# Juricic_Ulaz.net
KiCad netlist of a schematic drawn in Altium Designer
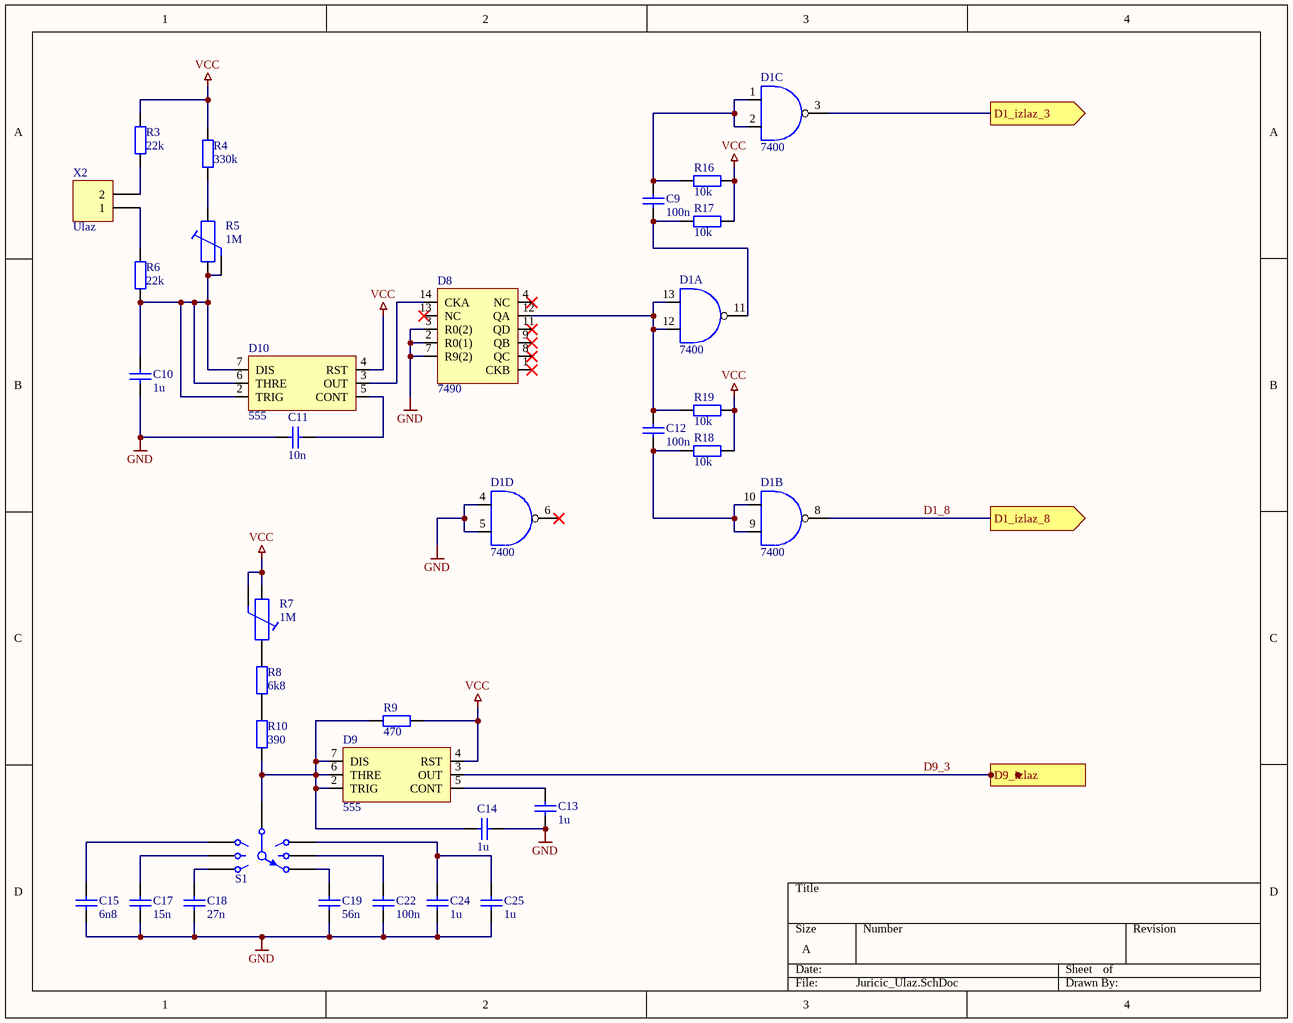
[diagram p0: Juricic_Ulaz.SchDoc]

(export (version "E")
  (design (tool "Eeschema 10.0.6"))
  (components
    (comp (ref "C9")
      (value "100n")
      (footprint "C0805")
      (description "100n capacitor")
      (fields (field (name "PUBLISHER") "Altium Limited"))
      (libsource (lib "Miscellaneous Devices") (part "Cap"))
    )
    (comp (ref "C10")
      (value "1u")
      (footprint "C0805")
      (description "1u capacitor")
      (fields (field (name "PUBLISHER") "Altium Limited"))
      (libsource (lib "Miscellaneous Devices") (part "Cap"))
    )
    (comp (ref "C11")
      (value "10n")
      (footprint "C0805")
      (description "10n capacitor")
      (fields (field (name "PUBLISHER") "Altium Limited"))
      (libsource (lib "Miscellaneous Devices") (part "Cap"))
    )
    (comp (ref "C12")
      (value "100n")
      (footprint "C0805")
      (description "100n capacitor")
      (fields (field (name "PUBLISHER") "Altium Limited"))
      (libsource (lib "Miscellaneous Devices") (part "Cap"))
    )
    (comp (ref "C13")
      (value "1u")
      (footprint "C0805")
      (description "1u capacitor")
      (fields (field (name "PUBLISHER") "Altium Limited"))
      (libsource (lib "Miscellaneous Devices") (part "Cap"))
    )
    (comp (ref "C14")
      (value "1u")
      (footprint "C0805")
      (description "1u capacitor")
      (fields (field (name "PUBLISHER") "Altium Limited"))
      (libsource (lib "Miscellaneous Devices") (part "Cap"))
    )
    (comp (ref "C15")
      (value "6n8")
      (footprint "C0805")
      (description "6n8 capacitor")
      (fields (field (name "PUBLISHER") "Altium Limited"))
      (libsource (lib "Miscellaneous Devices") (part "Cap"))
    )
    (comp (ref "C17")
      (value "15n")
      (footprint "C0805")
      (description "15n capacitor")
      (fields (field (name "PUBLISHER") "Altium Limited"))
      (libsource (lib "Miscellaneous Devices") (part "Cap"))
    )
    (comp (ref "C18")
      (value "27n")
      (footprint "C0805")
      (description "27n capacitor")
      (fields (field (name "PUBLISHER") "Altium Limited"))
      (libsource (lib "Miscellaneous Devices") (part "Cap"))
    )
    (comp (ref "C19")
      (value "56n")
      (footprint "C0805")
      (description "56n capacitor")
      (fields (field (name "PUBLISHER") "Altium Limited"))
      (libsource (lib "Miscellaneous Devices") (part "Cap"))
    )
    (comp (ref "C22")
      (value "100n")
      (footprint "C0805")
      (description "100n capacitor")
      (fields (field (name "PUBLISHER") "Altium Limited"))
      (libsource (lib "Miscellaneous Devices") (part "Cap"))
    )
    (comp (ref "C24")
      (value "1u")
      (footprint "C0805")
      (description "1u capacitor")
      (fields (field (name "PUBLISHER") "Altium Limited"))
      (libsource (lib "Miscellaneous Devices") (part "Cap"))
    )
    (comp (ref "C25")
      (value "1u")
      (footprint "C0805")
      (description "1u capacitor")
      (fields (field (name "PUBLISHER") "Altium Limited"))
      (libsource (lib "Miscellaneous Devices") (part "Cap"))
    )
    (comp (ref "D1")
      (value "7400")
      (footprint "DIP-14")
      (description "NI sklop")
      (libsource (lib "Indikator_lib") (part "7400"))
    )
    (comp (ref "D8")
      (value "7490")
      (footprint "DIP-14")
      (description "Dekadsko/binarno brojilo")
      (libsource (lib "Indikator_lib") (part "7490"))
    )
    (comp (ref "D9") (value "555") (footprint "DIP-8") (libsource (lib "Indikator_lib") (part "555")))
    (comp (ref "D10") (value "555") (footprint "DIP-8") (libsource (lib "Indikator_lib") (part "555")))
    (comp (ref "R3")
      (value "22k")
      (footprint "AXIAL-0.4")
      (description "22k resistor")
      (fields (field (name "PUBLISHER") "Altium Limited"))
      (libsource (lib "") (part "Res2_2"))
    )
    (comp (ref "R4")
      (value "330k")
      (footprint "AXIAL-0.4")
      (description "330k resistor")
      (fields (field (name "PUBLISHER") "Altium Limited"))
      (libsource (lib "") (part "Res2_2"))
    )
    (comp (ref "R5") (value "1M") (footprint "Trimmer") (libsource (lib "Juricic_Ivan") (part "Trimmer")))
    (comp (ref "R6")
      (value "22k")
      (footprint "AXIAL-0.4")
      (description "22k resistor")
      (fields (field (name "PUBLISHER") "Altium Limited"))
      (libsource (lib "Miscellaneous Devices") (part "Res2"))
    )
    (comp (ref "R7") (value "1M") (footprint "Trimmer") (libsource (lib "Juricic_Ivan") (part "Trimmer")))
    (comp (ref "R8")
      (value "6k8")
      (footprint "AXIAL-0.4")
      (description "6k8 resistor")
      (fields (field (name "PUBLISHER") "Altium Limited"))
      (libsource (lib "Miscellaneous Devices") (part "Res2"))
    )
    (comp (ref "R9")
      (value "470")
      (footprint "AXIAL-0.4")
      (description "470 resistor")
      (fields (field (name "PUBLISHER") "Altium Limited"))
      (libsource (lib "") (part "Res2_1"))
    )
    (comp (ref "R10")
      (value "390")
      (footprint "AXIAL-0.4")
      (description "390 resistor")
      (fields (field (name "PUBLISHER") "Altium Limited"))
      (libsource (lib "Miscellaneous Devices") (part "Res2"))
    )
    (comp (ref "R16")
      (value "10k")
      (footprint "AXIAL-0.4")
      (description "10k resistor")
      (fields (field (name "PUBLISHER") "Altium Limited"))
      (libsource (lib "") (part "Res2_1"))
    )
    (comp (ref "R17")
      (value "10k")
      (footprint "AXIAL-0.4")
      (description "10k resistor")
      (fields (field (name "PUBLISHER") "Altium Limited"))
      (libsource (lib "") (part "Res2_1"))
    )
    (comp (ref "R18")
      (value "10k")
      (footprint "AXIAL-0.4")
      (description "10k resistor")
      (fields (field (name "PUBLISHER") "Altium Limited"))
      (libsource (lib "") (part "Res2_1"))
    )
    (comp (ref "R19")
      (value "10k")
      (footprint "AXIAL-0.4")
      (description "10k resistor")
      (fields (field (name "PUBLISHER") "Altium Limited"))
      (libsource (lib "") (part "Res2_1"))
    )
    (comp (ref "S1")
      (value "SW-6WAY")
      (footprint "SW-7")
      (description "6 Way Switch")
      (fields (field (name "PUBLISHER") "Altium Limited"))
      (libsource (lib "Miscellaneous Devices") (part "SW-6WAY"))
    )
    (comp (ref "X2")
      (value "Ulaz")
      (footprint "HDR1X2")
      (description "Header, 2-Pin")
      (fields (field (name "PUBLISHER") "Altium Limited"))
      (libsource (lib "Miscellaneous Connectors") (part "Header 2"))
    )
  )
  (nets
    (net (code "1") (name "/D1_8") (class "Default")
      (node (ref "D1") (pin "8") (pinfunction "18_8") (pintype "passive"))
    )
    (net (code "2") (name "/D1_izlaz_3") (class "Default")
      (node (ref "D1") (pin "3") (pinfunction "18_3") (pintype "passive"))
    )
    (net (code "3") (name "/D9_3") (class "Default")
      (node (ref "D9") (pin "3") (pinfunction "OUT_3") (pintype "passive"))
    )
    (net (code "4") (name "GND") (class "Default")
      (node (ref "C10") (pin "1") (pinfunction "1_1") (pintype "passive"))
      (node (ref "C11") (pin "2") (pinfunction "2_2") (pintype "passive"))
      (node (ref "C13") (pin "2") (pinfunction "2_2") (pintype "passive"))
      (node (ref "C14") (pin "1") (pinfunction "1_1") (pintype "passive"))
      (node (ref "C15") (pin "1") (pinfunction "1_1") (pintype "passive"))
      (node (ref "C17") (pin "1") (pinfunction "1_1") (pintype "passive"))
      (node (ref "C18") (pin "1") (pinfunction "1_1") (pintype "passive"))
      (node (ref "C19") (pin "1") (pinfunction "1_1") (pintype "passive"))
      (node (ref "C22") (pin "1") (pinfunction "1_1") (pintype "passive"))
      (node (ref "C24") (pin "1") (pinfunction "1_1") (pintype "passive"))
      (node (ref "C25") (pin "1") (pinfunction "1_1") (pintype "passive"))
      (node (ref "D1") (pin "4") (pinfunction "18_4") (pintype "passive"))
      (node (ref "D1") (pin "5") (pinfunction "18_5") (pintype "passive"))
      (node (ref "D8") (pin "2") (pinfunction "R0(1)_2") (pintype "passive"))
      (node (ref "D8") (pin "3") (pinfunction "R0(2)_3") (pintype "passive"))
      (node (ref "D8") (pin "7") (pinfunction "R9(2)_7") (pintype "passive"))
    )
    (net (code "5") (name "Net-(C9-Pad1)") (class "Default")
      (node (ref "C9") (pin "1") (pinfunction "1_1") (pintype "passive"))
      (node (ref "D1") (pin "11") (pinfunction "18_11") (pintype "passive"))
      (node (ref "R17") (pin "1") (pinfunction "1_1") (pintype "passive"))
    )
    (net (code "6") (name "Net-(C9-Pad2)") (class "Default")
      (node (ref "C9") (pin "2") (pinfunction "2_2") (pintype "passive"))
      (node (ref "D1") (pin "1") (pinfunction "18_1") (pintype "passive"))
      (node (ref "D1") (pin "2") (pinfunction "18_2") (pintype "passive"))
      (node (ref "R16") (pin "1") (pinfunction "1_1") (pintype "passive"))
    )
    (net (code "7") (name "Net-(C12-Pad1)") (class "Default")
      (node (ref "C12") (pin "1") (pinfunction "1_1") (pintype "passive"))
      (node (ref "D1") (pin "10") (pinfunction "18_10") (pintype "passive"))
      (node (ref "D1") (pin "9") (pinfunction "18_9") (pintype "passive"))
      (node (ref "R18") (pin "1") (pinfunction "1_1") (pintype "passive"))
    )
    (net (code "8") (name "Net-(C15-Pad2)") (class "Default")
      (node (ref "C15") (pin "2") (pinfunction "2_2") (pintype "passive"))
      (node (ref "S1") (pin "1") (pinfunction "1_1") (pintype "passive"))
    )
    (net (code "9") (name "Net-(C17-Pad2)") (class "Default")
      (node (ref "C17") (pin "2") (pinfunction "2_2") (pintype "passive"))
      (node (ref "S1") (pin "2") (pinfunction "2_2") (pintype "passive"))
    )
    (net (code "10") (name "Net-(C18-Pad2)") (class "Default")
      (node (ref "C18") (pin "2") (pinfunction "2_2") (pintype "passive"))
      (node (ref "S1") (pin "3") (pinfunction "3_3") (pintype "passive"))
    )
    (net (code "11") (name "Net-(C19-Pad2)") (class "Default")
      (node (ref "C19") (pin "2") (pinfunction "2_2") (pintype "passive"))
      (node (ref "S1") (pin "6") (pinfunction "6_6") (pintype "passive"))
    )
    (net (code "12") (name "Net-(C22-Pad2)") (class "Default")
      (node (ref "C22") (pin "2") (pinfunction "2_2") (pintype "passive"))
      (node (ref "S1") (pin "5") (pinfunction "5_5") (pintype "passive"))
    )
    (net (code "13") (name "Net-(C24-Pad2)") (class "Default")
      (node (ref "C24") (pin "2") (pinfunction "2_2") (pintype "passive"))
      (node (ref "C25") (pin "2") (pinfunction "2_2") (pintype "passive"))
      (node (ref "S1") (pin "4") (pinfunction "4_4") (pintype "passive"))
    )
    (net (code "14") (name "Net-(D8-QA)") (class "Default")
      (node (ref "C12") (pin "2") (pinfunction "2_2") (pintype "passive"))
      (node (ref "D1") (pin "12") (pinfunction "18_12") (pintype "passive"))
      (node (ref "D1") (pin "13") (pinfunction "18_13") (pintype "passive"))
      (node (ref "D8") (pin "12") (pinfunction "QA_12") (pintype "passive"))
      (node (ref "R19") (pin "1") (pinfunction "1_1") (pintype "passive"))
    )
    (net (code "15") (name "Net-(D9-CONT)") (class "Default")
      (node (ref "C13") (pin "1") (pinfunction "1_1") (pintype "passive"))
      (node (ref "D9") (pin "5") (pinfunction "CONT_5") (pintype "passive"))
    )
    (net (code "16") (name "Net-(D9-DIS)") (class "Default")
      (node (ref "C14") (pin "2") (pinfunction "2_2") (pintype "passive"))
      (node (ref "D9") (pin "2") (pinfunction "TRIG_2") (pintype "passive"))
      (node (ref "D9") (pin "6") (pinfunction "THRE_6") (pintype "passive"))
      (node (ref "D9") (pin "7") (pinfunction "DIS_7") (pintype "passive"))
      (node (ref "R10") (pin "2") (pinfunction "2_2") (pintype "passive"))
      (node (ref "R9") (pin "1") (pinfunction "1_1") (pintype "passive"))
      (node (ref "S1") (pin "7") (pinfunction "7_7") (pintype "passive"))
    )
    (net (code "17") (name "Net-(D10-CONT)") (class "Default")
      (node (ref "C11") (pin "1") (pinfunction "1_1") (pintype "passive"))
      (node (ref "D10") (pin "5") (pinfunction "CONT_5") (pintype "passive"))
    )
    (net (code "18") (name "Net-(D10-DIS)") (class "Default")
      (node (ref "C10") (pin "2") (pinfunction "2_2") (pintype "passive"))
      (node (ref "D10") (pin "2") (pinfunction "TRIG_2") (pintype "passive"))
      (node (ref "D10") (pin "6") (pinfunction "THRE_6") (pintype "passive"))
      (node (ref "D10") (pin "7") (pinfunction "DIS_7") (pintype "passive"))
      (node (ref "R5") (pin "2") (pinfunction "2_2") (pintype "passive"))
      (node (ref "R5") (pin "3") (pinfunction "3_3") (pintype "passive"))
      (node (ref "R6") (pin "2") (pinfunction "2_2") (pintype "passive"))
    )
    (net (code "19") (name "Net-(D10-OUT)") (class "Default")
      (node (ref "D10") (pin "3") (pinfunction "OUT_3") (pintype "passive"))
      (node (ref "D8") (pin "14") (pinfunction "CKA_14") (pintype "passive"))
    )
    (net (code "20") (name "Net-(R3-Pad1)") (class "Default")
      (node (ref "R3") (pin "1") (pinfunction "1_1") (pintype "passive"))
      (node (ref "X2") (pin "2") (pinfunction "2_2") (pintype "passive"))
    )
    (net (code "21") (name "Net-(R4-Pad1)") (class "Default")
      (node (ref "R4") (pin "1") (pinfunction "1_1") (pintype "passive"))
      (node (ref "R5") (pin "1") (pinfunction "1_1") (pintype "passive"))
    )
    (net (code "22") (name "Net-(R6-Pad1)") (class "Default")
      (node (ref "R6") (pin "1") (pinfunction "1_1") (pintype "passive"))
      (node (ref "X2") (pin "1") (pinfunction "1_1") (pintype "passive"))
    )
    (net (code "23") (name "Net-(R7-Pad1)") (class "Default")
      (node (ref "R7") (pin "1") (pinfunction "1_1") (pintype "passive"))
      (node (ref "R8") (pin "1") (pinfunction "1_1") (pintype "passive"))
    )
    (net (code "24") (name "Net-(R10-Pad1)") (class "Default")
      (node (ref "R10") (pin "1") (pinfunction "1_1") (pintype "passive"))
      (node (ref "R8") (pin "2") (pinfunction "2_2") (pintype "passive"))
    )
    (net (code "25") (name "VCC") (class "Default")
      (node (ref "D10") (pin "4") (pinfunction "RST_4") (pintype "passive"))
      (node (ref "D9") (pin "4") (pinfunction "RST_4") (pintype "passive"))
      (node (ref "R16") (pin "2") (pinfunction "2_2") (pintype "passive"))
      (node (ref "R17") (pin "2") (pinfunction "2_2") (pintype "passive"))
      (node (ref "R18") (pin "2") (pinfunction "2_2") (pintype "passive"))
      (node (ref "R19") (pin "2") (pinfunction "2_2") (pintype "passive"))
      (node (ref "R3") (pin "2") (pinfunction "2_2") (pintype "passive"))
      (node (ref "R4") (pin "2") (pinfunction "2_2") (pintype "passive"))
      (node (ref "R7") (pin "2") (pinfunction "2_2") (pintype "passive"))
      (node (ref "R7") (pin "3") (pinfunction "3_3") (pintype "passive"))
      (node (ref "R9") (pin "2") (pinfunction "2_2") (pintype "passive"))
    )
    (net (code "26") (name "unconnected-(D1D-18-Pad6)") (class "Default")
      (node (ref "D1") (pin "6") (pinfunction "18_6") (pintype "passive+no_connect"))
    )
    (net (code "27") (name "unconnected-(D8-CKB-Pad1)") (class "Default")
      (node (ref "D8") (pin "1") (pinfunction "CKB_1") (pintype "passive+no_connect"))
    )
    (net (code "28") (name "unconnected-(D8-NC-Pad4)") (class "Default")
      (node (ref "D8") (pin "4") (pinfunction "NC_4") (pintype "passive+no_connect"))
    )
    (net (code "29") (name "unconnected-(D8-NC-Pad13)") (class "Default")
      (node (ref "D8") (pin "13") (pinfunction "NC_13") (pintype "passive+no_connect"))
    )
    (net (code "30") (name "unconnected-(D8-QB-Pad9)") (class "Default")
      (node (ref "D8") (pin "9") (pinfunction "QB_9") (pintype "passive+no_connect"))
    )
    (net (code "31") (name "unconnected-(D8-QC-Pad8)") (class "Default")
      (node (ref "D8") (pin "8") (pinfunction "QC_8") (pintype "passive+no_connect"))
    )
    (net (code "32") (name "unconnected-(D8-QD-Pad11)") (class "Default")
      (node (ref "D8") (pin "11") (pinfunction "QD_11") (pintype "passive+no_connect"))
    )
  )
)
